# bucket.net
KiCad netlist of a schematic drawn in EAGLE
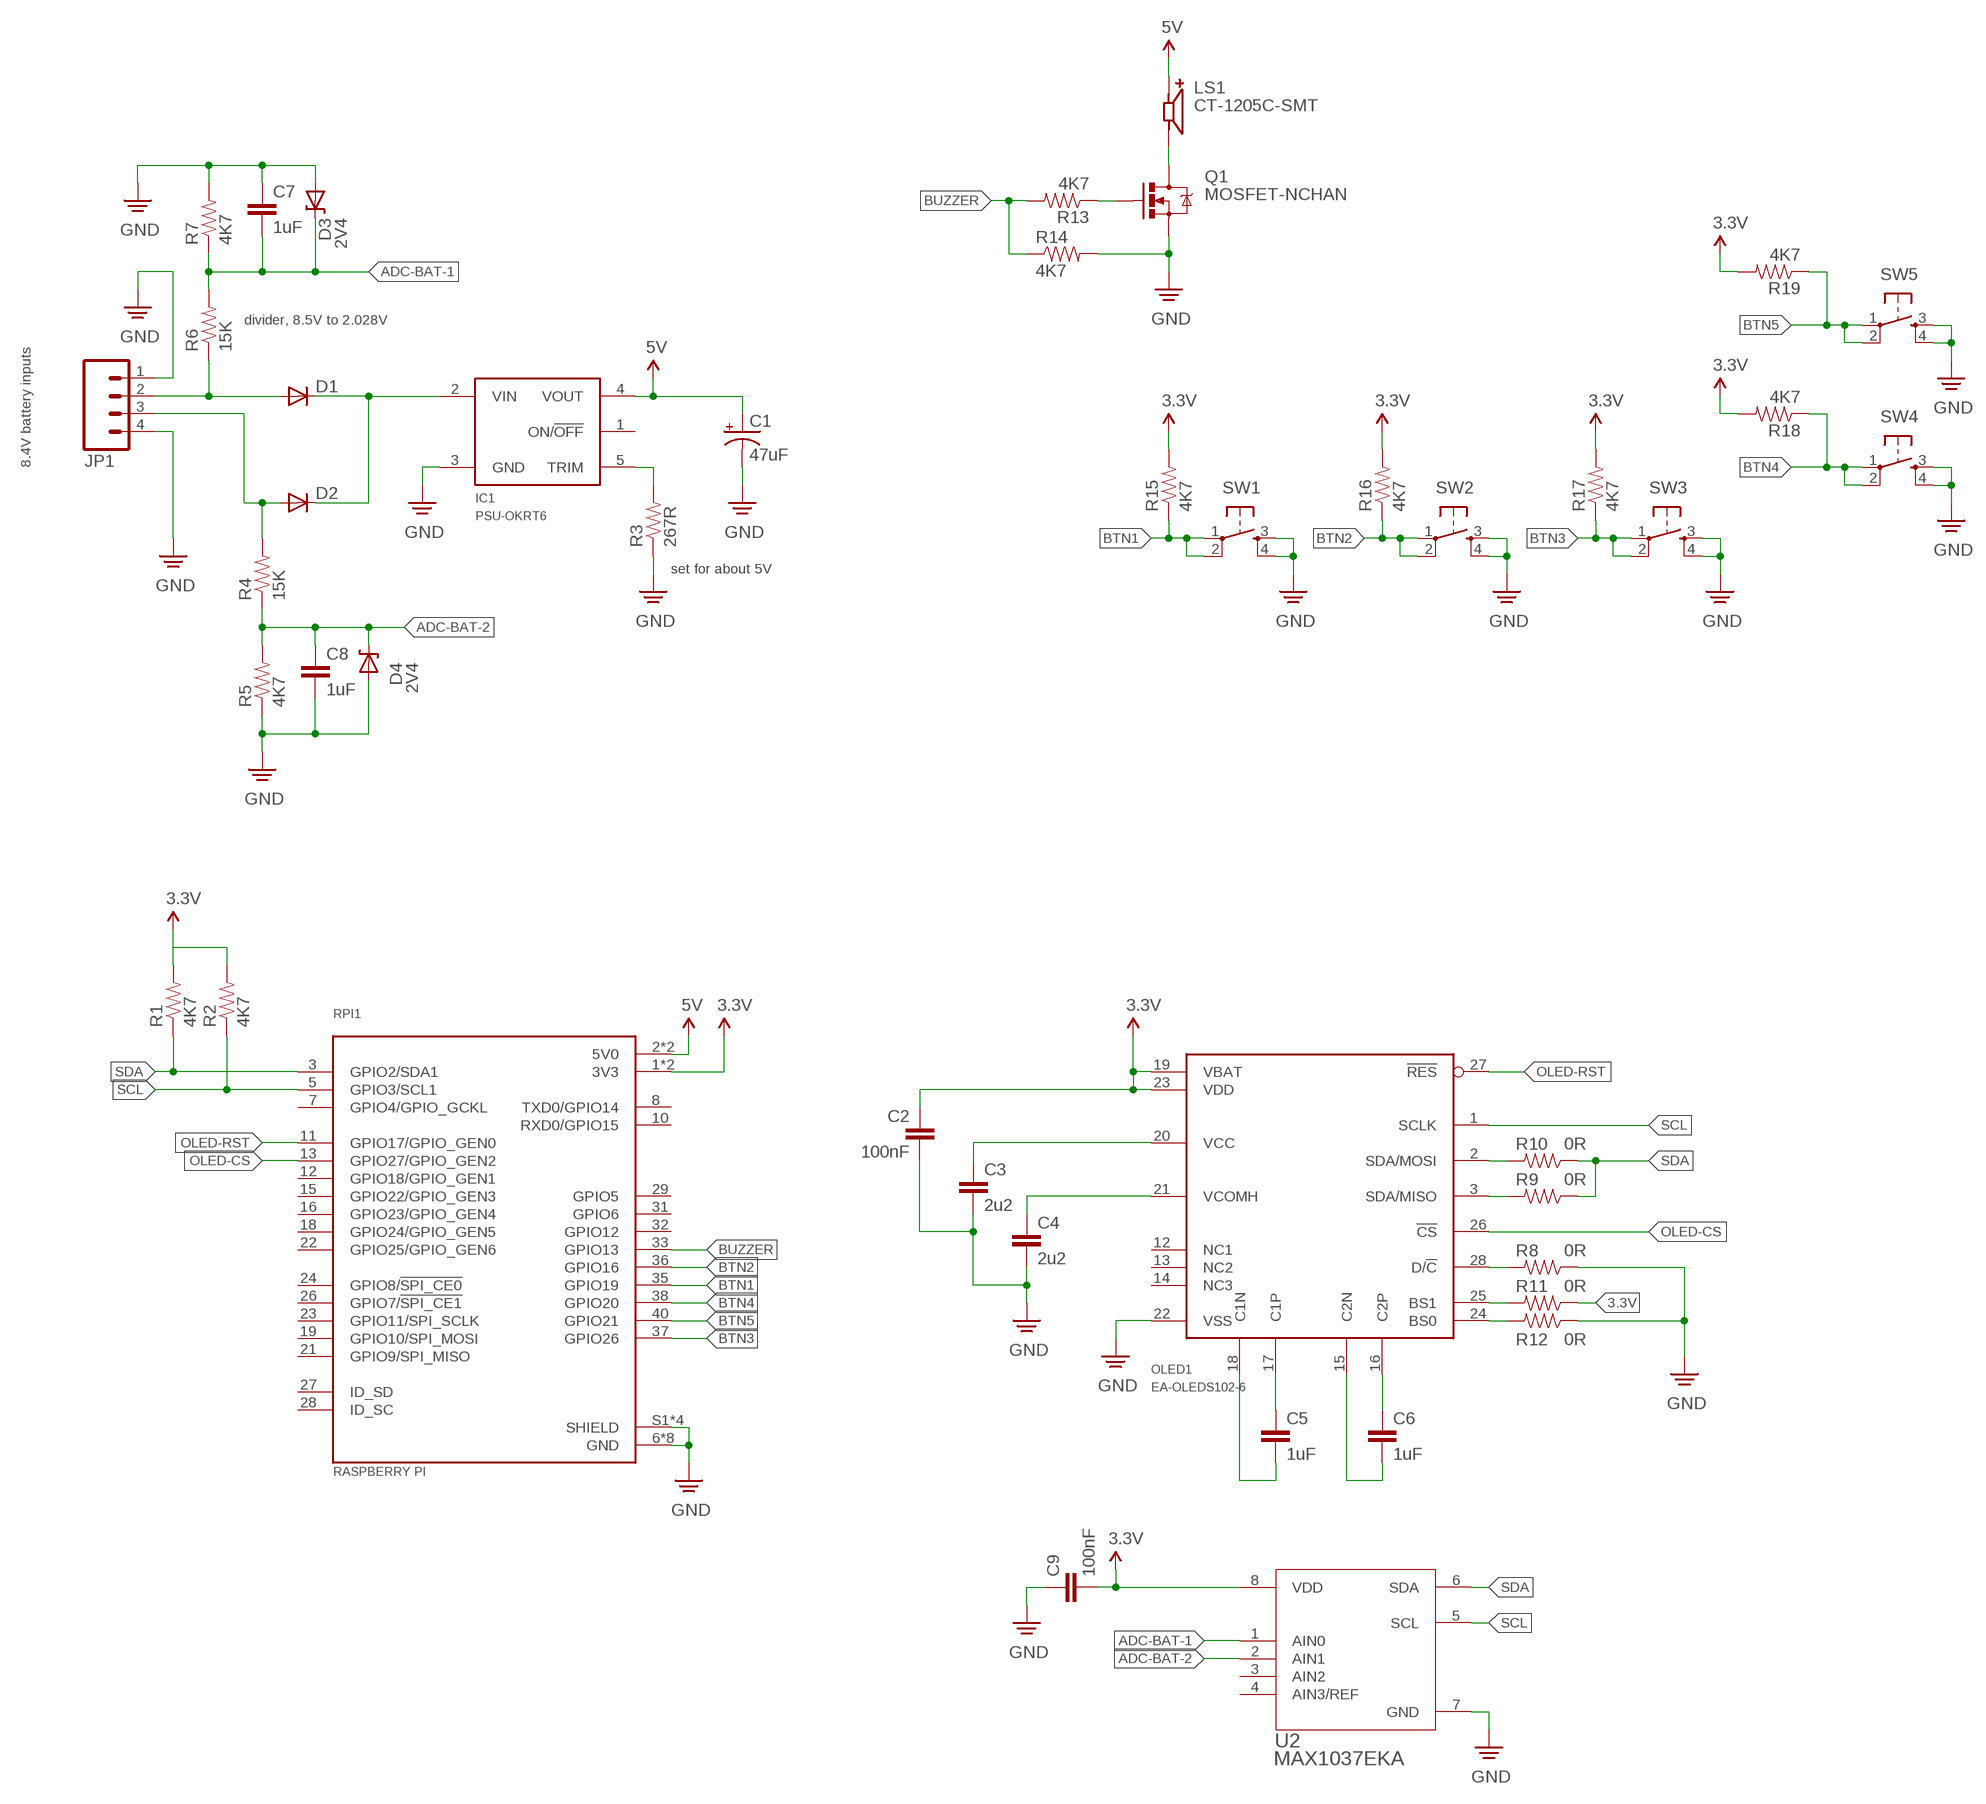
[diagram p0: schematic, sheet 1]

(export (version "E")
  (design (tool "Eeschema 10.0.6"))
  (components
    (comp (ref "C1")
      (value "47uF")
      (footprint "eagle-import:PANASONIC_D")
      (libsource (lib "eagle-import") (part "CAP_POLD"))
    )
    (comp (ref "C2")
      (value "100nF")
      (footprint "eagle-import:0603-CAP")
      (libsource (lib "eagle-import") (part "CAP0603-CAP"))
    )
    (comp (ref "C3")
      (value "2u2")
      (footprint "eagle-import:0603-CAP")
      (libsource (lib "eagle-import") (part "CAP0603-CAP"))
    )
    (comp (ref "C4")
      (value "2u2")
      (footprint "eagle-import:0603-CAP")
      (libsource (lib "eagle-import") (part "CAP0603-CAP"))
    )
    (comp (ref "C5")
      (value "1uF")
      (footprint "eagle-import:0603-CAP")
      (libsource (lib "eagle-import") (part "CAP0603-CAP"))
    )
    (comp (ref "C6")
      (value "1uF")
      (footprint "eagle-import:0603-CAP")
      (libsource (lib "eagle-import") (part "CAP0603-CAP"))
    )
    (comp (ref "C7")
      (value "1uF")
      (footprint "eagle-import:0603-CAP")
      (libsource (lib "eagle-import") (part "CAP0603-CAP"))
    )
    (comp (ref "C8")
      (value "1uF")
      (footprint "eagle-import:0603-CAP")
      (libsource (lib "eagle-import") (part "CAP0603-CAP"))
    )
    (comp (ref "C9")
      (value "100nF")
      (footprint "eagle-import:0603-CAP")
      (libsource (lib "eagle-import") (part "CAP0603-CAP"))
    )
    (comp (ref "D1")
      (value "DIODESMB")
      (footprint "eagle-import:SMB-DIODE")
      (libsource (lib "eagle-import") (part "DIODESMB"))
    )
    (comp (ref "D2")
      (value "DIODESMB")
      (footprint "eagle-import:SMB-DIODE")
      (libsource (lib "eagle-import") (part "DIODESMB"))
    )
    (comp (ref "D3")
      (value "2V4")
      (footprint "eagle-import:SOD-323")
      (libsource (lib "eagle-import") (part "DIODE-ZENER-SOD323"))
    )
    (comp (ref "D4")
      (value "2V4")
      (footprint "eagle-import:SOD-323")
      (libsource (lib "eagle-import") (part "DIODE-ZENER-SOD323"))
    )
    (comp (ref "IC1")
      (value "PSU-OKRT6")
      (footprint "eagle-import:PSU-OKRT6")
      (libsource (lib "eagle-import") (part "PSU-OKRT6"))
    )
    (comp (ref "JP1")
      (value "M04-AMPMODUMTE-TH-ANG")
      (footprint "eagle-import:M04-AMPMODUMTE-TH-ANG")
      (libsource (lib "eagle-import") (part "M04-AMPMODUMTE-TH-ANG"))
    )
    (comp (ref "LS1")
      (value "CT-1205C-SMT")
      (footprint "eagle-import:CUI_CT-1205C-SMT")
      (fields (field (name "MF") "CUI DEVICES"))
      (libsource (lib "eagle-import") (part "CT-1205C-SMT"))
    )
    (comp (ref "OLED1")
      (value "EA-OLEDS102-6")
      (footprint "eagle-import:EA-OLEDS102-6")
      (libsource (lib "eagle-import") (part "EA-OLEDS102-6"))
    )
    (comp (ref "Q1")
      (value "MOSFET-NCHAN")
      (footprint "eagle-import:SOT23-3")
      (libsource (lib "eagle-import") (part "MOSFET-NCHANNELSMD"))
    )
    (comp (ref "R1")
      (value "4K7")
      (footprint "eagle-import:0603-RES")
      (libsource (lib "eagle-import") (part "RESISTOR0603-RES"))
    )
    (comp (ref "R2")
      (value "4K7")
      (footprint "eagle-import:0603-RES")
      (libsource (lib "eagle-import") (part "RESISTOR0603-RES"))
    )
    (comp (ref "R3")
      (value "267R")
      (footprint "eagle-import:0603-RES")
      (libsource (lib "eagle-import") (part "RESISTOR0603-RES"))
    )
    (comp (ref "R4")
      (value "15K")
      (footprint "eagle-import:0603-RES")
      (libsource (lib "eagle-import") (part "RESISTOR0603-RES"))
    )
    (comp (ref "R5")
      (value "4K7")
      (footprint "eagle-import:0603-RES")
      (libsource (lib "eagle-import") (part "RESISTOR0603-RES"))
    )
    (comp (ref "R6")
      (value "15K")
      (footprint "eagle-import:0603-RES")
      (libsource (lib "eagle-import") (part "RESISTOR0603-RES"))
    )
    (comp (ref "R7")
      (value "4K7")
      (footprint "eagle-import:0603-RES")
      (libsource (lib "eagle-import") (part "RESISTOR0603-RES"))
    )
    (comp (ref "R8")
      (value "0R")
      (footprint "eagle-import:0603-RES")
      (libsource (lib "eagle-import") (part "RESISTOR0603-RES"))
    )
    (comp (ref "R9")
      (value "0R")
      (footprint "eagle-import:0603-RES")
      (libsource (lib "eagle-import") (part "RESISTOR0603-RES"))
    )
    (comp (ref "R10")
      (value "0R")
      (footprint "eagle-import:0603-RES")
      (libsource (lib "eagle-import") (part "RESISTOR0603-RES"))
    )
    (comp (ref "R11")
      (value "0R")
      (footprint "eagle-import:0603-RES")
      (libsource (lib "eagle-import") (part "RESISTOR0603-RES"))
    )
    (comp (ref "R12")
      (value "0R")
      (footprint "eagle-import:0603-RES")
      (libsource (lib "eagle-import") (part "RESISTOR0603-RES"))
    )
    (comp (ref "R13")
      (value "4K7")
      (footprint "eagle-import:0603-RES")
      (libsource (lib "eagle-import") (part "RESISTOR0603-RES"))
    )
    (comp (ref "R14")
      (value "4K7")
      (footprint "eagle-import:0603-RES")
      (libsource (lib "eagle-import") (part "RESISTOR0603-RES"))
    )
    (comp (ref "R15")
      (value "4K7")
      (footprint "eagle-import:0603-RES")
      (libsource (lib "eagle-import") (part "RESISTOR0603-RES"))
    )
    (comp (ref "R16")
      (value "4K7")
      (footprint "eagle-import:0603-RES")
      (libsource (lib "eagle-import") (part "RESISTOR0603-RES"))
    )
    (comp (ref "R17")
      (value "4K7")
      (footprint "eagle-import:0603-RES")
      (libsource (lib "eagle-import") (part "RESISTOR0603-RES"))
    )
    (comp (ref "R18")
      (value "4K7")
      (footprint "eagle-import:0603-RES")
      (libsource (lib "eagle-import") (part "RESISTOR0603-RES"))
    )
    (comp (ref "R19")
      (value "4K7")
      (footprint "eagle-import:0603-RES")
      (libsource (lib "eagle-import") (part "RESISTOR0603-RES"))
    )
    (comp (ref "RPI1")
      (value "RASPBERRY PI")
      (footprint "eagle-import:MODULE_RASPBERRY_PI_3_MODEL_B+")
      (libsource (lib "eagle-import") (part "RASPBERRY_PI_3_MODEL_B+"))
    )
    (comp (ref "SW1")
      (value "TAC_SWITCHPTH")
      (footprint "eagle-import:TACTILE-PTH")
      (libsource (lib "eagle-import") (part "TAC_SWITCHPTH"))
    )
    (comp (ref "SW2")
      (value "TAC_SWITCHPTH")
      (footprint "eagle-import:TACTILE-PTH")
      (libsource (lib "eagle-import") (part "TAC_SWITCHPTH"))
    )
    (comp (ref "SW3")
      (value "TAC_SWITCHPTH")
      (footprint "eagle-import:TACTILE-PTH")
      (libsource (lib "eagle-import") (part "TAC_SWITCHPTH"))
    )
    (comp (ref "SW4")
      (value "TAC_SWITCHPTH")
      (footprint "eagle-import:TACTILE-PTH")
      (libsource (lib "eagle-import") (part "TAC_SWITCHPTH"))
    )
    (comp (ref "SW5")
      (value "TAC_SWITCHPTH")
      (footprint "eagle-import:TACTILE-PTH")
      (libsource (lib "eagle-import") (part "TAC_SWITCHPTH"))
    )
    (comp (ref "U2")
      (value "MAX1037EKA")
      (footprint "eagle-import:21-0078H")
      (fields (field (name "MF") "Maxim Integrated"))
      (libsource (lib "eagle-import") (part "MAX1037EKA"))
    )
  )
  (nets
    (net (code "1") (name "3.3V") (class "Default")
      (node (ref "C2") (pin "1") (pinfunction "1_1") (pintype "passive"))
      (node (ref "C9") (pin "2") (pinfunction "2_2") (pintype "passive"))
      (node (ref "OLED1") (pin "19") (pinfunction "VBAT_19") (pintype "input"))
      (node (ref "OLED1") (pin "23") (pinfunction "VDD_23") (pintype "input"))
      (node (ref "R1") (pin "2") (pinfunction "2_2") (pintype "passive"))
      (node (ref "R11") (pin "1") (pinfunction "1_1") (pintype "passive"))
      (node (ref "R15") (pin "2") (pinfunction "2_2") (pintype "passive"))
      (node (ref "R16") (pin "2") (pinfunction "2_2") (pintype "passive"))
      (node (ref "R17") (pin "2") (pinfunction "2_2") (pintype "passive"))
      (node (ref "R18") (pin "2") (pinfunction "2_2") (pintype "passive"))
      (node (ref "R19") (pin "2") (pinfunction "2_2") (pintype "passive"))
      (node (ref "R2") (pin "2") (pinfunction "2_2") (pintype "passive"))
      (node (ref "RPI1") (pin "1") (pinfunction "3V3_1") (pintype "power_in"))
      (node (ref "RPI1") (pin "17") (pinfunction "3V3_17") (pintype "power_in"))
      (node (ref "U2") (pin "8") (pinfunction "VDD_8") (pintype "power_in"))
    )
    (net (code "2") (name "5V") (class "Default")
      (node (ref "C1") (pin "+") (pinfunction "+_+") (pintype "passive"))
      (node (ref "IC1") (pin "4") (pinfunction "VOUT_4") (pintype "output"))
      (node (ref "LS1") (pin "1") (pinfunction "1_1") (pintype "passive"))
      (node (ref "RPI1") (pin "2") (pinfunction "5V0_2") (pintype "power_in"))
      (node (ref "RPI1") (pin "4") (pinfunction "5V0_4") (pintype "power_in"))
    )
    (net (code "3") (name "ADC-BAT-1") (class "Default")
      (node (ref "C7") (pin "2") (pinfunction "2_2") (pintype "passive"))
      (node (ref "D3") (pin "1") (pinfunction "C_1") (pintype "passive"))
      (node (ref "R6") (pin "2") (pinfunction "2_2") (pintype "passive"))
      (node (ref "R7") (pin "1") (pinfunction "1_1") (pintype "passive"))
      (node (ref "U2") (pin "1") (pinfunction "AIN0_1") (pintype "bidirectional"))
    )
    (net (code "4") (name "ADC-BAT-2") (class "Default")
      (node (ref "C8") (pin "1") (pinfunction "1_1") (pintype "passive"))
      (node (ref "D4") (pin "1") (pinfunction "C_1") (pintype "passive"))
      (node (ref "R4") (pin "1") (pinfunction "1_1") (pintype "passive"))
      (node (ref "R5") (pin "2") (pinfunction "2_2") (pintype "passive"))
      (node (ref "U2") (pin "2") (pinfunction "AIN1_2") (pintype "bidirectional"))
    )
    (net (code "5") (name "BTN1") (class "Default")
      (node (ref "R15") (pin "1") (pinfunction "1_1") (pintype "passive"))
      (node (ref "RPI1") (pin "35") (pinfunction "GPIO19_35") (pintype "bidirectional"))
      (node (ref "SW1") (pin "1") (pinfunction "1_1") (pintype "passive"))
      (node (ref "SW1") (pin "2") (pinfunction "2_2") (pintype "passive"))
    )
    (net (code "6") (name "BTN2") (class "Default")
      (node (ref "R16") (pin "1") (pinfunction "1_1") (pintype "passive"))
      (node (ref "RPI1") (pin "36") (pinfunction "GPIO16_36") (pintype "bidirectional"))
      (node (ref "SW2") (pin "1") (pinfunction "1_1") (pintype "passive"))
      (node (ref "SW2") (pin "2") (pinfunction "2_2") (pintype "passive"))
    )
    (net (code "7") (name "BTN3") (class "Default")
      (node (ref "R17") (pin "1") (pinfunction "1_1") (pintype "passive"))
      (node (ref "RPI1") (pin "37") (pinfunction "GPIO26_37") (pintype "bidirectional"))
      (node (ref "SW3") (pin "1") (pinfunction "1_1") (pintype "passive"))
      (node (ref "SW3") (pin "2") (pinfunction "2_2") (pintype "passive"))
    )
    (net (code "8") (name "BTN4") (class "Default")
      (node (ref "R18") (pin "1") (pinfunction "1_1") (pintype "passive"))
      (node (ref "RPI1") (pin "38") (pinfunction "GPIO20_38") (pintype "bidirectional"))
      (node (ref "SW4") (pin "1") (pinfunction "1_1") (pintype "passive"))
      (node (ref "SW4") (pin "2") (pinfunction "2_2") (pintype "passive"))
    )
    (net (code "9") (name "BTN5") (class "Default")
      (node (ref "R19") (pin "1") (pinfunction "1_1") (pintype "passive"))
      (node (ref "RPI1") (pin "40") (pinfunction "GPIO21_40") (pintype "bidirectional"))
      (node (ref "SW5") (pin "1") (pinfunction "1_1") (pintype "passive"))
      (node (ref "SW5") (pin "2") (pinfunction "2_2") (pintype "passive"))
    )
    (net (code "10") (name "BUZZER") (class "Default")
      (node (ref "R13") (pin "2") (pinfunction "2_2") (pintype "passive"))
      (node (ref "R14") (pin "1") (pinfunction "1_1") (pintype "passive"))
      (node (ref "RPI1") (pin "33") (pinfunction "GPIO13_33") (pintype "bidirectional"))
    )
    (net (code "11") (name "GND") (class "Default")
      (node (ref "C1") (pin "-") (pinfunction "-_-") (pintype "passive"))
      (node (ref "C2") (pin "2") (pinfunction "2_2") (pintype "passive"))
      (node (ref "C3") (pin "2") (pinfunction "2_2") (pintype "passive"))
      (node (ref "C4") (pin "2") (pinfunction "2_2") (pintype "passive"))
      (node (ref "C7") (pin "1") (pinfunction "1_1") (pintype "passive"))
      (node (ref "C8") (pin "2") (pinfunction "2_2") (pintype "passive"))
      (node (ref "C9") (pin "1") (pinfunction "1_1") (pintype "passive"))
      (node (ref "D3") (pin "2") (pinfunction "A_2") (pintype "passive"))
      (node (ref "D4") (pin "2") (pinfunction "A_2") (pintype "passive"))
      (node (ref "IC1") (pin "3") (pinfunction "GND_3") (pintype "input"))
      (node (ref "JP1") (pin "1") (pinfunction "1_1") (pintype "passive"))
      (node (ref "JP1") (pin "4") (pinfunction "4_4") (pintype "passive"))
      (node (ref "OLED1") (pin "22") (pinfunction "VSS_22") (pintype "input"))
      (node (ref "Q1") (pin "2") (pinfunction "S_2") (pintype "passive"))
      (node (ref "R12") (pin "1") (pinfunction "1_1") (pintype "passive"))
      (node (ref "R14") (pin "2") (pinfunction "2_2") (pintype "passive"))
      (node (ref "R3") (pin "1") (pinfunction "1_1") (pintype "passive"))
      (node (ref "R5") (pin "1") (pinfunction "1_1") (pintype "passive"))
      (node (ref "R7") (pin "2") (pinfunction "2_2") (pintype "passive"))
      (node (ref "R8") (pin "1") (pinfunction "1_1") (pintype "passive"))
      (node (ref "RPI1") (pin "14") (pinfunction "GND_14") (pintype "power_in"))
      (node (ref "RPI1") (pin "20") (pinfunction "GND_20") (pintype "power_in"))
      (node (ref "RPI1") (pin "25") (pinfunction "GND_25") (pintype "power_in"))
      (node (ref "RPI1") (pin "30") (pinfunction "GND_30") (pintype "power_in"))
      (node (ref "RPI1") (pin "34") (pinfunction "GND_34") (pintype "power_in"))
      (node (ref "RPI1") (pin "39") (pinfunction "GND_39") (pintype "power_in"))
      (node (ref "RPI1") (pin "6") (pinfunction "GND_6") (pintype "power_in"))
      (node (ref "RPI1") (pin "9") (pinfunction "GND_9") (pintype "power_in"))
      (node (ref "RPI1") (pin "S1") (pinfunction "SHIELD_S1") (pintype "power_in"))
      (node (ref "RPI1") (pin "S2") (pinfunction "SHIELD_S2") (pintype "power_in"))
      (node (ref "RPI1") (pin "S3") (pinfunction "SHIELD_S3") (pintype "power_in"))
      (node (ref "RPI1") (pin "S4") (pinfunction "SHIELD_S4") (pintype "power_in"))
      (node (ref "SW1") (pin "3") (pinfunction "3_3") (pintype "passive"))
      (node (ref "SW1") (pin "4") (pinfunction "4_4") (pintype "passive"))
      (node (ref "SW2") (pin "3") (pinfunction "3_3") (pintype "passive"))
      (node (ref "SW2") (pin "4") (pinfunction "4_4") (pintype "passive"))
      (node (ref "SW3") (pin "3") (pinfunction "3_3") (pintype "passive"))
      (node (ref "SW3") (pin "4") (pinfunction "4_4") (pintype "passive"))
      (node (ref "SW4") (pin "3") (pinfunction "3_3") (pintype "passive"))
      (node (ref "SW4") (pin "4") (pinfunction "4_4") (pintype "passive"))
      (node (ref "SW5") (pin "3") (pinfunction "3_3") (pintype "passive"))
      (node (ref "SW5") (pin "4") (pinfunction "4_4") (pintype "passive"))
      (node (ref "U2") (pin "7") (pinfunction "GND_7") (pintype "power_in"))
    )
    (net (code "12") (name "Net-(D1-PadA)") (class "Default")
      (node (ref "D1") (pin "A") (pinfunction "A_A") (pintype "passive"))
      (node (ref "JP1") (pin "2") (pinfunction "2_2") (pintype "passive"))
      (node (ref "R6") (pin "1") (pinfunction "1_1") (pintype "passive"))
    )
    (net (code "13") (name "Net-(D2-PadA)") (class "Default")
      (node (ref "D2") (pin "A") (pinfunction "A_A") (pintype "passive"))
      (node (ref "JP1") (pin "3") (pinfunction "3_3") (pintype "passive"))
      (node (ref "R4") (pin "2") (pinfunction "2_2") (pintype "passive"))
    )
    (net (code "14") (name "Net-(IC1-TRIM)") (class "Default")
      (node (ref "IC1") (pin "5") (pinfunction "TRIM_5") (pintype "bidirectional"))
      (node (ref "R3") (pin "2") (pinfunction "2_2") (pintype "passive"))
    )
    (net (code "15") (name "Net-(IC1-VIN)") (class "Default")
      (node (ref "D1") (pin "C") (pinfunction "C_C") (pintype "passive"))
      (node (ref "D2") (pin "C") (pinfunction "C_C") (pintype "passive"))
      (node (ref "IC1") (pin "2") (pinfunction "VIN_2") (pintype "input"))
    )
    (net (code "16") (name "Net-(OLED1-BS0)") (class "Default")
      (node (ref "OLED1") (pin "24") (pinfunction "BS0_24") (pintype "input"))
      (node (ref "R12") (pin "2") (pinfunction "2_2") (pintype "passive"))
    )
    (net (code "17") (name "Net-(OLED1-BS1)") (class "Default")
      (node (ref "OLED1") (pin "25") (pinfunction "BS1_25") (pintype "input"))
      (node (ref "R11") (pin "2") (pinfunction "2_2") (pintype "passive"))
    )
    (net (code "18") (name "Net-(OLED1-C1N)") (class "Default")
      (node (ref "C5") (pin "2") (pinfunction "2_2") (pintype "passive"))
      (node (ref "OLED1") (pin "18") (pinfunction "C1N_18") (pintype "bidirectional"))
    )
    (net (code "19") (name "Net-(OLED1-C1P)") (class "Default")
      (node (ref "C5") (pin "1") (pinfunction "1_1") (pintype "passive"))
      (node (ref "OLED1") (pin "17") (pinfunction "C1P_17") (pintype "bidirectional"))
    )
    (net (code "20") (name "Net-(OLED1-C2N)") (class "Default")
      (node (ref "C6") (pin "2") (pinfunction "2_2") (pintype "passive"))
      (node (ref "OLED1") (pin "15") (pinfunction "C2N_15") (pintype "bidirectional"))
    )
    (net (code "21") (name "Net-(OLED1-C2P)") (class "Default")
      (node (ref "C6") (pin "1") (pinfunction "1_1") (pintype "passive"))
      (node (ref "OLED1") (pin "16") (pinfunction "C2P_16") (pintype "bidirectional"))
    )
    (net (code "22") (name "Net-(OLED1-D{slash}~{C})") (class "Default")
      (node (ref "OLED1") (pin "28") (pinfunction "D/~{C}_28") (pintype "bidirectional"))
      (node (ref "R8") (pin "2") (pinfunction "2_2") (pintype "passive"))
    )
    (net (code "23") (name "Net-(OLED1-SDA{slash}MISO)") (class "Default")
      (node (ref "OLED1") (pin "3") (pinfunction "SDA/MISO_3") (pintype "bidirectional"))
      (node (ref "R9") (pin "2") (pinfunction "2_2") (pintype "passive"))
    )
    (net (code "24") (name "Net-(OLED1-SDA{slash}MOSI)") (class "Default")
      (node (ref "OLED1") (pin "2") (pinfunction "SDA/MOSI_2") (pintype "bidirectional"))
      (node (ref "R10") (pin "2") (pinfunction "2_2") (pintype "passive"))
    )
    (net (code "25") (name "Net-(OLED1-VCC)") (class "Default")
      (node (ref "C3") (pin "1") (pinfunction "1_1") (pintype "passive"))
      (node (ref "OLED1") (pin "20") (pinfunction "VCC_20") (pintype "bidirectional"))
    )
    (net (code "26") (name "Net-(OLED1-VCOMH)") (class "Default")
      (node (ref "C4") (pin "1") (pinfunction "1_1") (pintype "passive"))
      (node (ref "OLED1") (pin "21") (pinfunction "VCOMH_21") (pintype "bidirectional"))
    )
    (net (code "27") (name "Net-(Q1-D)") (class "Default")
      (node (ref "LS1") (pin "2") (pinfunction "2_2") (pintype "passive"))
      (node (ref "Q1") (pin "3") (pinfunction "D_3") (pintype "passive"))
    )
    (net (code "28") (name "Net-(Q1-G)") (class "Default")
      (node (ref "Q1") (pin "1") (pinfunction "G_1") (pintype "passive"))
      (node (ref "R13") (pin "1") (pinfunction "1_1") (pintype "passive"))
    )
    (net (code "29") (name "OLED-CS") (class "Default")
      (node (ref "OLED1") (pin "26") (pinfunction "~{CS}_26") (pintype "bidirectional"))
      (node (ref "RPI1") (pin "13") (pinfunction "GPIO27/GPIO_GEN2_13") (pintype "bidirectional"))
    )
    (net (code "30") (name "OLED-RST") (class "Default")
      (node (ref "OLED1") (pin "27") (pinfunction "~{RES}_27") (pintype "input"))
      (node (ref "RPI1") (pin "11") (pinfunction "GPIO17/GPIO_GEN0_11") (pintype "bidirectional"))
    )
    (net (code "31") (name "SCL") (class "Default")
      (node (ref "OLED1") (pin "1") (pinfunction "SCLK_1") (pintype "bidirectional"))
      (node (ref "R2") (pin "1") (pinfunction "1_1") (pintype "passive"))
      (node (ref "RPI1") (pin "5") (pinfunction "GPIO3/SCL1_5") (pintype "bidirectional"))
      (node (ref "U2") (pin "5") (pinfunction "SCL_5") (pintype "bidirectional"))
    )
    (net (code "32") (name "SDA") (class "Default")
      (node (ref "R1") (pin "1") (pinfunction "1_1") (pintype "passive"))
      (node (ref "R10") (pin "1") (pinfunction "1_1") (pintype "passive"))
      (node (ref "R9") (pin "1") (pinfunction "1_1") (pintype "passive"))
      (node (ref "RPI1") (pin "3") (pinfunction "GPIO2/SDA1_3") (pintype "bidirectional"))
      (node (ref "U2") (pin "6") (pinfunction "SDA_6") (pintype "bidirectional"))
    )
    (net (code "33") (name "unconnected-(IC1-ON{slash}~{OFF}-Pad1)") (class "Default")
      (node (ref "IC1") (pin "1") (pinfunction "ON/~{OFF}_1") (pintype "bidirectional"))
    )
    (net (code "34") (name "unconnected-(OLED1-NC1-Pad12)") (class "Default")
      (node (ref "OLED1") (pin "12") (pinfunction "NC1_12") (pintype "no_connect"))
    )
    (net (code "35") (name "unconnected-(OLED1-NC2-Pad13)") (class "Default")
      (node (ref "OLED1") (pin "13") (pinfunction "NC2_13") (pintype "no_connect"))
    )
    (net (code "36") (name "unconnected-(OLED1-NC3-Pad14)") (class "Default")
      (node (ref "OLED1") (pin "14") (pinfunction "NC3_14") (pintype "no_connect"))
    )
    (net (code "37") (name "unconnected-(RPI1-GPIO4{slash}GPIO_GCKL-Pad7)") (class "Default")
      (node (ref "RPI1") (pin "7") (pinfunction "GPIO4/GPIO_GCKL_7") (pintype "bidirectional"))
    )
    (net (code "38") (name "unconnected-(RPI1-GPIO5-Pad29)") (class "Default")
      (node (ref "RPI1") (pin "29") (pinfunction "GPIO5_29") (pintype "bidirectional"))
    )
    (net (code "39") (name "unconnected-(RPI1-GPIO6-Pad31)") (class "Default")
      (node (ref "RPI1") (pin "31") (pinfunction "GPIO6_31") (pintype "bidirectional"))
    )
    (net (code "40") (name "unconnected-(RPI1-GPIO7{slash}~{SPI_CE1}-Pad26)") (class "Default")
      (node (ref "RPI1") (pin "26") (pinfunction "GPIO7/~{SPI_CE1}_26") (pintype "bidirectional"))
    )
    (net (code "41") (name "unconnected-(RPI1-GPIO8{slash}~{SPI_CE0}-Pad24)") (class "Default")
      (node (ref "RPI1") (pin "24") (pinfunction "GPIO8/~{SPI_CE0}_24") (pintype "bidirectional"))
    )
    (net (code "42") (name "unconnected-(RPI1-GPIO9{slash}SPI_MISO-Pad21)") (class "Default")
      (node (ref "RPI1") (pin "21") (pinfunction "GPIO9/SPI_MISO_21") (pintype "bidirectional"))
    )
    (net (code "43") (name "unconnected-(RPI1-GPIO10{slash}SPI_MOSI-Pad19)") (class "Default")
      (node (ref "RPI1") (pin "19") (pinfunction "GPIO10/SPI_MOSI_19") (pintype "bidirectional"))
    )
    (net (code "44") (name "unconnected-(RPI1-GPIO11{slash}SPI_SCLK-Pad23)") (class "Default")
      (node (ref "RPI1") (pin "23") (pinfunction "GPIO11/SPI_SCLK_23") (pintype "bidirectional"))
    )
    (net (code "45") (name "unconnected-(RPI1-GPIO12-Pad32)") (class "Default")
      (node (ref "RPI1") (pin "32") (pinfunction "GPIO12_32") (pintype "bidirectional"))
    )
    (net (code "46") (name "unconnected-(RPI1-GPIO18{slash}GPIO_GEN1-Pad12)") (class "Default")
      (node (ref "RPI1") (pin "12") (pinfunction "GPIO18/GPIO_GEN1_12") (pintype "bidirectional"))
    )
    (net (code "47") (name "unconnected-(RPI1-GPIO22{slash}GPIO_GEN3-Pad15)") (class "Default")
      (node (ref "RPI1") (pin "15") (pinfunction "GPIO22/GPIO_GEN3_15") (pintype "bidirectional"))
    )
    (net (code "48") (name "unconnected-(RPI1-GPIO23{slash}GPIO_GEN4-Pad16)") (class "Default")
      (node (ref "RPI1") (pin "16") (pinfunction "GPIO23/GPIO_GEN4_16") (pintype "bidirectional"))
    )
    (net (code "49") (name "unconnected-(RPI1-GPIO24{slash}GPIO_GEN5-Pad18)") (class "Default")
      (node (ref "RPI1") (pin "18") (pinfunction "GPIO24/GPIO_GEN5_18") (pintype "bidirectional"))
    )
    (net (code "50") (name "unconnected-(RPI1-GPIO25{slash}GPIO_GEN6-Pad22)") (class "Default")
      (node (ref "RPI1") (pin "22") (pinfunction "GPIO25/GPIO_GEN6_22") (pintype "bidirectional"))
    )
    (net (code "51") (name "unconnected-(RPI1-ID_SC-Pad28)") (class "Default")
      (node (ref "RPI1") (pin "28") (pinfunction "ID_SC_28") (pintype "bidirectional"))
    )
    (net (code "52") (name "unconnected-(RPI1-ID_SD-Pad27)") (class "Default")
      (node (ref "RPI1") (pin "27") (pinfunction "ID_SD_27") (pintype "bidirectional"))
    )
    (net (code "53") (name "unconnected-(RPI1-RXD0{slash}GPIO15-Pad10)") (class "Default")
      (node (ref "RPI1") (pin "10") (pinfunction "RXD0/GPIO15_10") (pintype "bidirectional"))
    )
    (net (code "54") (name "unconnected-(RPI1-TXD0{slash}GPIO14-Pad8)") (class "Default")
      (node (ref "RPI1") (pin "8") (pinfunction "TXD0/GPIO14_8") (pintype "bidirectional"))
    )
    (net (code "55") (name "unconnected-(U2-AIN2-Pad3)") (class "Default")
      (node (ref "U2") (pin "3") (pinfunction "AIN2_3") (pintype "bidirectional"))
    )
    (net (code "56") (name "unconnected-(U2-AIN3{slash}REF-Pad4)") (class "Default")
      (node (ref "U2") (pin "4") (pinfunction "AIN3/REF_4") (pintype "bidirectional"))
    )
  )
)
